# DESIGN8SM.net
KiCad netlist of a schematic drawn in EAGLE
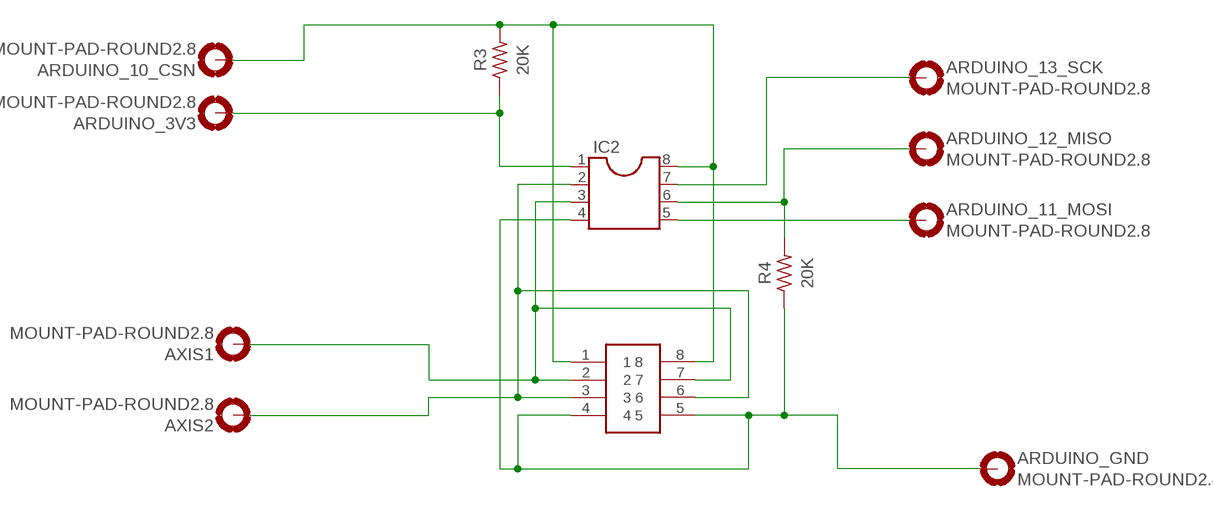
[diagram p0: schematic, sheet 1]

(export (version "E")
  (design (tool "Eeschema 10.0.6"))
  (components
    (comp (ref "ARDUINO_3V3")
      (value "MOUNT-PAD-ROUND2.8")
      (footprint "eagle-import:2,8-PAD")
      (libsource (lib "eagle-import") (part "MOUNT-PAD-ROUND2.8"))
    )
    (comp (ref "ARDUINO_10_CSN")
      (value "MOUNT-PAD-ROUND2.8")
      (footprint "eagle-import:2,8-PAD")
      (libsource (lib "eagle-import") (part "MOUNT-PAD-ROUND2.8"))
    )
    (comp (ref "ARDUINO_11_MOSI")
      (value "MOUNT-PAD-ROUND2.8")
      (footprint "eagle-import:2,8-PAD")
      (libsource (lib "eagle-import") (part "MOUNT-PAD-ROUND2.8"))
    )
    (comp (ref "ARDUINO_12_MISO")
      (value "MOUNT-PAD-ROUND2.8")
      (footprint "eagle-import:2,8-PAD")
      (libsource (lib "eagle-import") (part "MOUNT-PAD-ROUND2.8"))
    )
    (comp (ref "ARDUINO_13_SCK")
      (value "MOUNT-PAD-ROUND2.8")
      (footprint "eagle-import:2,8-PAD")
      (libsource (lib "eagle-import") (part "MOUNT-PAD-ROUND2.8"))
    )
    (comp (ref "ARDUINO_GND")
      (value "MOUNT-PAD-ROUND2.8")
      (footprint "eagle-import:2,8-PAD")
      (libsource (lib "eagle-import") (part "MOUNT-PAD-ROUND2.8"))
    )
    (comp (ref "AXIS1")
      (value "MOUNT-PAD-ROUND2.8")
      (footprint "eagle-import:2,8-PAD")
      (libsource (lib "eagle-import") (part "MOUNT-PAD-ROUND2.8"))
    )
    (comp (ref "AXIS2")
      (value "MOUNT-PAD-ROUND2.8")
      (footprint "eagle-import:2,8-PAD")
      (libsource (lib "eagle-import") (part "MOUNT-PAD-ROUND2.8"))
    )
    (comp (ref "IC2")
      (value "DIL8S")
      (footprint "eagle-import:SOCKET-08")
      (libsource (lib "eagle-import") (part "DIL8S"))
    )
    (comp (ref "R3")
      (value "20K")
      (footprint "eagle-import:RESAD1176W63L850D250B")
      (libsource (lib "eagle-import") (part "R-USAXIAL-11.7MM-PITCH_"))
    )
    (comp (ref "R4")
      (value "20K")
      (footprint "eagle-import:RESAD1176W63L850D250B")
      (libsource (lib "eagle-import") (part "R-USAXIAL-11.7MM-PITCH_"))
    )
    (comp (ref "U$2")
      (value "JOYSTICK")
      (footprint "eagle-import:JOYSTICK")
      (libsource (lib "eagle-import") (part "JOYSTICK"))
    )
  )
  (nets
    (net (code "1") (name "Net-(ARDUINO_3V3-MOUNT)") (class "Default")
      (node (ref "ARDUINO_3V3") (pin "B2,8") (pinfunction "MOUNT_B2,8") (pintype "passive"))
      (node (ref "IC2") (pin "1") (pinfunction "1_1") (pintype "passive"))
      (node (ref "R3") (pin "1") (pinfunction "1_1") (pintype "passive"))
    )
    (net (code "2") (name "Net-(ARDUINO_10_CSN-MOUNT)") (class "Default")
      (node (ref "ARDUINO_10_CSN") (pin "B2,8") (pinfunction "MOUNT_B2,8") (pintype "passive"))
      (node (ref "IC2") (pin "8") (pinfunction "8_8") (pintype "passive"))
      (node (ref "R3") (pin "2") (pinfunction "2_2") (pintype "passive"))
      (node (ref "U$2") (pin "1") (pinfunction "1_1") (pintype "bidirectional"))
      (node (ref "U$2") (pin "8") (pinfunction "8_8") (pintype "bidirectional"))
    )
    (net (code "3") (name "Net-(ARDUINO_11_MOSI-MOUNT)") (class "Default")
      (node (ref "ARDUINO_11_MOSI") (pin "B2,8") (pinfunction "MOUNT_B2,8") (pintype "passive"))
      (node (ref "IC2") (pin "5") (pinfunction "5_5") (pintype "passive"))
    )
    (net (code "4") (name "Net-(ARDUINO_12_MISO-MOUNT)") (class "Default")
      (node (ref "ARDUINO_12_MISO") (pin "B2,8") (pinfunction "MOUNT_B2,8") (pintype "passive"))
      (node (ref "IC2") (pin "6") (pinfunction "6_6") (pintype "passive"))
      (node (ref "R4") (pin "2") (pinfunction "2_2") (pintype "passive"))
    )
    (net (code "5") (name "Net-(ARDUINO_13_SCK-MOUNT)") (class "Default")
      (node (ref "ARDUINO_13_SCK") (pin "B2,8") (pinfunction "MOUNT_B2,8") (pintype "passive"))
      (node (ref "IC2") (pin "7") (pinfunction "7_7") (pintype "passive"))
    )
    (net (code "6") (name "Net-(ARDUINO_GND-MOUNT)") (class "Default")
      (node (ref "ARDUINO_GND") (pin "B2,8") (pinfunction "MOUNT_B2,8") (pintype "passive"))
      (node (ref "IC2") (pin "4") (pinfunction "4_4") (pintype "passive"))
      (node (ref "R4") (pin "1") (pinfunction "1_1") (pintype "passive"))
      (node (ref "U$2") (pin "4") (pinfunction "4_4") (pintype "bidirectional"))
      (node (ref "U$2") (pin "5") (pinfunction "5_5") (pintype "bidirectional"))
    )
    (net (code "7") (name "Net-(AXIS1-MOUNT)") (class "Default")
      (node (ref "AXIS1") (pin "B2,8") (pinfunction "MOUNT_B2,8") (pintype "passive"))
      (node (ref "IC2") (pin "3") (pinfunction "3_3") (pintype "passive"))
      (node (ref "U$2") (pin "2") (pinfunction "2_2") (pintype "bidirectional"))
      (node (ref "U$2") (pin "7") (pinfunction "7_7") (pintype "bidirectional"))
    )
    (net (code "8") (name "Net-(AXIS2-MOUNT)") (class "Default")
      (node (ref "AXIS2") (pin "B2,8") (pinfunction "MOUNT_B2,8") (pintype "passive"))
      (node (ref "IC2") (pin "2") (pinfunction "2_2") (pintype "passive"))
      (node (ref "U$2") (pin "3") (pinfunction "3_3") (pintype "bidirectional"))
      (node (ref "U$2") (pin "6") (pinfunction "6_6") (pintype "bidirectional"))
    )
  )
)
